# test1.net
KiCad netlist of a schematic drawn in EAGLE
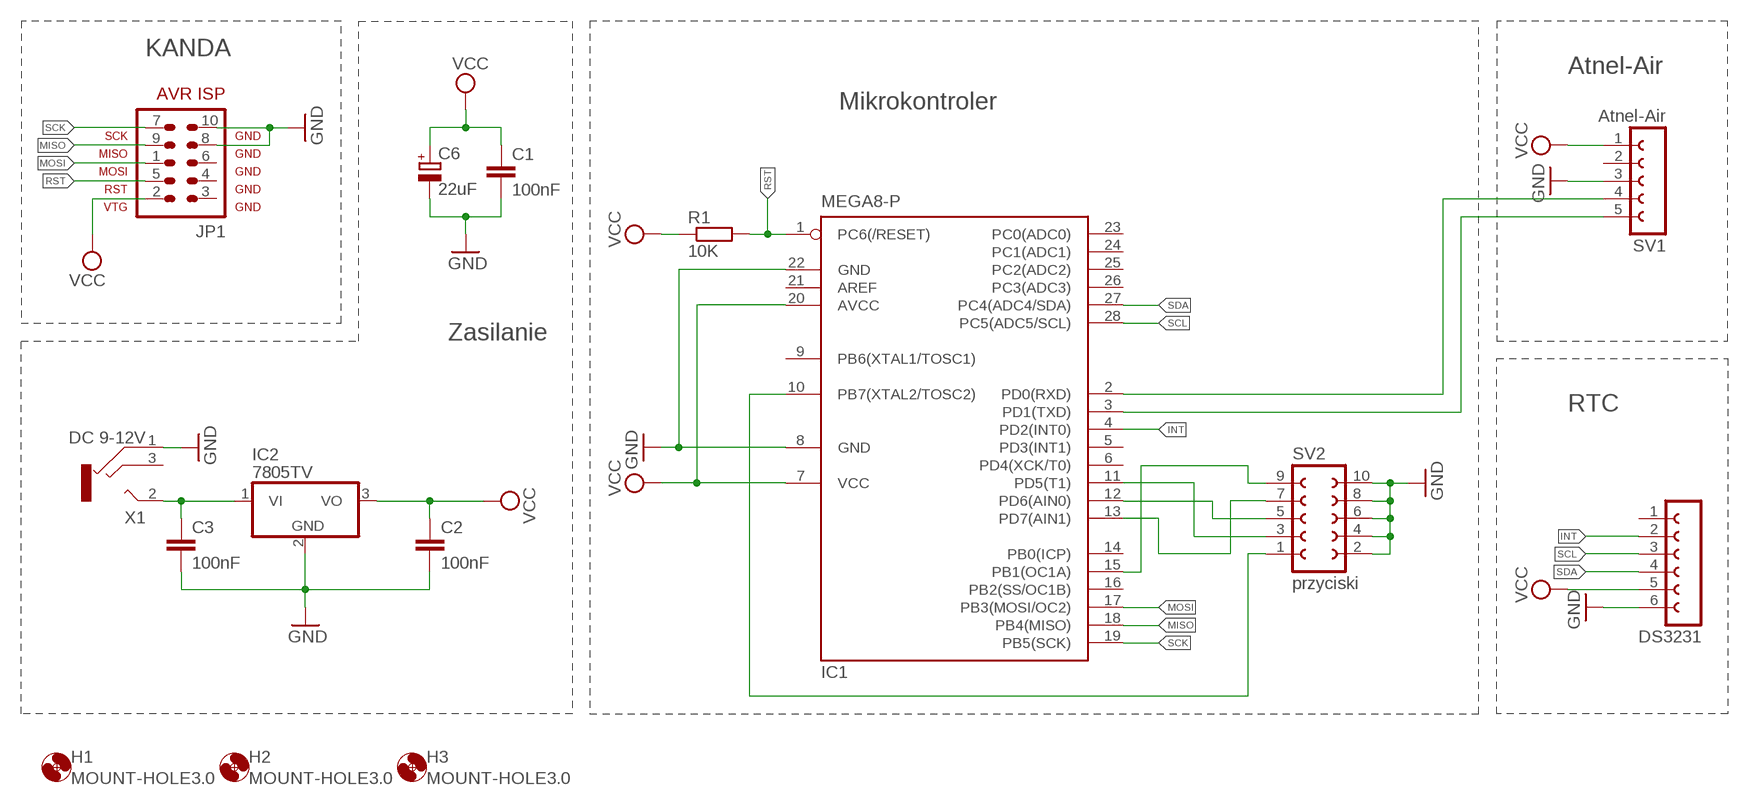
[diagram p0: schematic, sheet 1]

(export (version "E")
  (design (tool "Eeschema 10.0.6"))
  (components
    (comp (ref "C1")
      (value "100nF")
      (footprint "eagle-import:C025-024X044")
      (libsource (lib "eagle-import") (part "C-EU025-024X044"))
    )
    (comp (ref "C2")
      (value "100nF")
      (footprint "eagle-import:C025-024X044")
      (libsource (lib "eagle-import") (part "C-EU025-024X044"))
    )
    (comp (ref "C3")
      (value "100nF")
      (footprint "eagle-import:C025-024X044")
      (libsource (lib "eagle-import") (part "C-EU025-024X044"))
    )
    (comp (ref "C6")
      (value "22uF")
      (footprint "eagle-import:B45181A")
      (libsource (lib "eagle-import") (part "CPOL-EUB45181A"))
    )
    (comp (ref "DS3231")
      (value "FE06-1")
      (footprint "eagle-import:FE06")
      (libsource (lib "eagle-import") (part "FE06-1"))
    )
    (comp (ref "H1")
      (value "MOUNT-HOLE3.0")
      (footprint "eagle-import:3,0")
      (libsource (lib "eagle-import") (part "MOUNT-HOLE3.0"))
    )
    (comp (ref "H2")
      (value "MOUNT-HOLE3.0")
      (footprint "eagle-import:3,0")
      (libsource (lib "eagle-import") (part "MOUNT-HOLE3.0"))
    )
    (comp (ref "H3")
      (value "MOUNT-HOLE3.0")
      (footprint "eagle-import:3,0")
      (libsource (lib "eagle-import") (part "MOUNT-HOLE3.0"))
    )
    (comp (ref "IC1")
      (value "MEGA8-P")
      (footprint "eagle-import:DIL28-3")
      (libsource (lib "eagle-import") (part "MEGA8-P"))
    )
    (comp (ref "IC2")
      (value "7805TV")
      (footprint "eagle-import:TO220V")
      (libsource (lib "eagle-import") (part "78TV05"))
    )
    (comp (ref "JP1")
      (value "AVR-ISP-10")
      (footprint "eagle-import:AVR-ISP-10")
      (libsource (lib "eagle-import") (part "AVR-ISP-10"))
    )
    (comp (ref "R1")
      (value "10K")
      (footprint "eagle-import:0204V")
      (libsource (lib "eagle-import") (part "R-EU_0204/2V"))
    )
    (comp (ref "SV1")
      (value "Atnel-Air")
      (footprint "eagle-import:FE05-1")
      (libsource (lib "eagle-import") (part "FE05-1"))
    )
    (comp (ref "SV2")
      (value "przyciski")
      (footprint "eagle-import:FE05-2")
      (libsource (lib "eagle-import") (part "FE05-2"))
    )
    (comp (ref "X1")
      (value "DC 9-12V")
      (footprint "eagle-import:1501_05")
      (libsource (lib "eagle-import") (part "1501_04"))
    )
  )
  (nets
    (net (code "1") (name "GND") (class "Default")
      (node (ref "C1") (pin "2") (pinfunction "2_2") (pintype "passive"))
      (node (ref "C2") (pin "2") (pinfunction "2_2") (pintype "passive"))
      (node (ref "C3") (pin "2") (pinfunction "2_2") (pintype "passive"))
      (node (ref "C6") (pin "-") (pinfunction "-_-") (pintype "passive"))
      (node (ref "DS3231") (pin "6") (pinfunction "6_6") (pintype "passive"))
      (node (ref "IC1") (pin "22") (pinfunction "GND_22") (pintype "power_in"))
      (node (ref "IC1") (pin "8") (pinfunction "GND_8") (pintype "power_in"))
      (node (ref "IC2") (pin "2") (pinfunction "GND_2") (pintype "passive"))
      (node (ref "JP1") (pin "10") (pinfunction "10_10") (pintype "passive"))
      (node (ref "JP1") (pin "8") (pinfunction "8_8") (pintype "passive"))
      (node (ref "SV1") (pin "3") (pinfunction "3_3") (pintype "passive"))
      (node (ref "SV2") (pin "10") (pinfunction "10_10") (pintype "passive"))
      (node (ref "SV2") (pin "2") (pinfunction "2_2") (pintype "passive"))
      (node (ref "SV2") (pin "4") (pinfunction "4_4") (pintype "passive"))
      (node (ref "SV2") (pin "6") (pinfunction "6_6") (pintype "passive"))
      (node (ref "SV2") (pin "8") (pinfunction "8_8") (pintype "passive"))
      (node (ref "X1") (pin "1") (pinfunction "1_1") (pintype "passive"))
    )
    (net (code "2") (name "INT") (class "Default")
      (node (ref "DS3231") (pin "2") (pinfunction "2_2") (pintype "passive"))
      (node (ref "IC1") (pin "4") (pinfunction "PD2(INT0)_4") (pintype "bidirectional"))
    )
    (net (code "3") (name "MISO") (class "Default")
      (node (ref "IC1") (pin "18") (pinfunction "PB4(MISO)_18") (pintype "bidirectional"))
      (node (ref "JP1") (pin "9") (pinfunction "9_9") (pintype "passive"))
    )
    (net (code "4") (name "MOSI") (class "Default")
      (node (ref "IC1") (pin "17") (pinfunction "PB3(MOSI/OC2)_17") (pintype "bidirectional"))
      (node (ref "JP1") (pin "1") (pinfunction "1_1") (pintype "passive"))
    )
    (net (code "5") (name "Net-(IC1-PB1(OC1A))") (class "Default")
      (node (ref "IC1") (pin "15") (pinfunction "PB1(OC1A)_15") (pintype "bidirectional"))
      (node (ref "SV2") (pin "9") (pinfunction "9_9") (pintype "passive"))
    )
    (net (code "6") (name "Net-(IC1-PB7(XTAL2{slash}TOSC2))") (class "Default")
      (node (ref "IC1") (pin "10") (pinfunction "PB7(XTAL2/TOSC2)_10") (pintype "bidirectional"))
      (node (ref "SV2") (pin "1") (pinfunction "1_1") (pintype "passive"))
    )
    (net (code "7") (name "Net-(IC1-PD0(RXD))") (class "Default")
      (node (ref "IC1") (pin "2") (pinfunction "PD0(RXD)_2") (pintype "bidirectional"))
      (node (ref "SV1") (pin "4") (pinfunction "4_4") (pintype "passive"))
    )
    (net (code "8") (name "Net-(IC1-PD1(TXD))") (class "Default")
      (node (ref "IC1") (pin "3") (pinfunction "PD1(TXD)_3") (pintype "bidirectional"))
      (node (ref "SV1") (pin "5") (pinfunction "5_5") (pintype "passive"))
    )
    (net (code "9") (name "Net-(IC1-PD5(T1))") (class "Default")
      (node (ref "IC1") (pin "11") (pinfunction "PD5(T1)_11") (pintype "bidirectional"))
      (node (ref "SV2") (pin "3") (pinfunction "3_3") (pintype "passive"))
    )
    (net (code "10") (name "Net-(IC1-PD6(AIN0))") (class "Default")
      (node (ref "IC1") (pin "12") (pinfunction "PD6(AIN0)_12") (pintype "bidirectional"))
      (node (ref "SV2") (pin "5") (pinfunction "5_5") (pintype "passive"))
    )
    (net (code "11") (name "Net-(IC1-PD7(AIN1))") (class "Default")
      (node (ref "IC1") (pin "13") (pinfunction "PD7(AIN1)_13") (pintype "bidirectional"))
      (node (ref "SV2") (pin "7") (pinfunction "7_7") (pintype "passive"))
    )
    (net (code "12") (name "Net-(IC2-VI)") (class "Default")
      (node (ref "C3") (pin "1") (pinfunction "1_1") (pintype "passive"))
      (node (ref "IC2") (pin "1") (pinfunction "VI_1") (pintype "input"))
      (node (ref "X1") (pin "2") (pinfunction "2_2") (pintype "passive"))
    )
    (net (code "13") (name "RST") (class "Default")
      (node (ref "IC1") (pin "1") (pinfunction "PC6(/RESET)_1") (pintype "bidirectional"))
      (node (ref "JP1") (pin "5") (pinfunction "5_5") (pintype "passive"))
      (node (ref "R1") (pin "2") (pinfunction "2_2") (pintype "passive"))
    )
    (net (code "14") (name "SCK") (class "Default")
      (node (ref "IC1") (pin "19") (pinfunction "PB5(SCK)_19") (pintype "bidirectional"))
      (node (ref "JP1") (pin "7") (pinfunction "7_7") (pintype "passive"))
    )
    (net (code "15") (name "SCL") (class "Default")
      (node (ref "DS3231") (pin "3") (pinfunction "3_3") (pintype "passive"))
      (node (ref "IC1") (pin "28") (pinfunction "PC5(ADC5/SCL)_28") (pintype "bidirectional"))
    )
    (net (code "16") (name "SDA") (class "Default")
      (node (ref "DS3231") (pin "4") (pinfunction "4_4") (pintype "passive"))
      (node (ref "IC1") (pin "27") (pinfunction "PC4(ADC4/SDA)_27") (pintype "bidirectional"))
    )
    (net (code "17") (name "VCC") (class "Default")
      (node (ref "C1") (pin "1") (pinfunction "1_1") (pintype "passive"))
      (node (ref "C2") (pin "1") (pinfunction "1_1") (pintype "passive"))
      (node (ref "C6") (pin "+") (pinfunction "+_+") (pintype "passive"))
      (node (ref "DS3231") (pin "5") (pinfunction "5_5") (pintype "passive"))
      (node (ref "IC1") (pin "20") (pinfunction "AVCC_20") (pintype "power_in"))
      (node (ref "IC1") (pin "7") (pinfunction "VCC_7") (pintype "power_in"))
      (node (ref "IC2") (pin "3") (pinfunction "VO_3") (pintype "passive"))
      (node (ref "JP1") (pin "2") (pinfunction "2_2") (pintype "passive"))
      (node (ref "R1") (pin "1") (pinfunction "1_1") (pintype "passive"))
      (node (ref "SV1") (pin "1") (pinfunction "1_1") (pintype "passive"))
    )
    (net (code "18") (name "unconnected-(DS3231-Pad1)") (class "Default")
      (node (ref "DS3231") (pin "1") (pinfunction "1_1") (pintype "passive"))
    )
    (net (code "19") (name "unconnected-(IC1-AREF-Pad21)") (class "Default")
      (node (ref "IC1") (pin "21") (pinfunction "AREF_21") (pintype "passive"))
    )
    (net (code "20") (name "unconnected-(IC1-PB0(ICP)-Pad14)") (class "Default")
      (node (ref "IC1") (pin "14") (pinfunction "PB0(ICP)_14") (pintype "bidirectional"))
    )
    (net (code "21") (name "unconnected-(IC1-PB2(SS{slash}OC1B)-Pad16)") (class "Default")
      (node (ref "IC1") (pin "16") (pinfunction "PB2(SS/OC1B)_16") (pintype "bidirectional"))
    )
    (net (code "22") (name "unconnected-(IC1-PB6(XTAL1{slash}TOSC1)-Pad9)") (class "Default")
      (node (ref "IC1") (pin "9") (pinfunction "PB6(XTAL1/TOSC1)_9") (pintype "bidirectional"))
    )
    (net (code "23") (name "unconnected-(IC1-PC0(ADC0)-Pad23)") (class "Default")
      (node (ref "IC1") (pin "23") (pinfunction "PC0(ADC0)_23") (pintype "bidirectional"))
    )
    (net (code "24") (name "unconnected-(IC1-PC1(ADC1)-Pad24)") (class "Default")
      (node (ref "IC1") (pin "24") (pinfunction "PC1(ADC1)_24") (pintype "bidirectional"))
    )
    (net (code "25") (name "unconnected-(IC1-PC2(ADC2)-Pad25)") (class "Default")
      (node (ref "IC1") (pin "25") (pinfunction "PC2(ADC2)_25") (pintype "bidirectional"))
    )
    (net (code "26") (name "unconnected-(IC1-PC3(ADC3)-Pad26)") (class "Default")
      (node (ref "IC1") (pin "26") (pinfunction "PC3(ADC3)_26") (pintype "bidirectional"))
    )
    (net (code "27") (name "unconnected-(IC1-PD3(INT1)-Pad5)") (class "Default")
      (node (ref "IC1") (pin "5") (pinfunction "PD3(INT1)_5") (pintype "bidirectional"))
    )
    (net (code "28") (name "unconnected-(IC1-PD4(XCK{slash}T0)-Pad6)") (class "Default")
      (node (ref "IC1") (pin "6") (pinfunction "PD4(XCK/T0)_6") (pintype "bidirectional"))
    )
    (net (code "29") (name "unconnected-(JP1-Pad3)") (class "Default")
      (node (ref "JP1") (pin "3") (pinfunction "3_3") (pintype "passive"))
    )
    (net (code "30") (name "unconnected-(JP1-Pad4)") (class "Default")
      (node (ref "JP1") (pin "4") (pinfunction "4_4") (pintype "passive"))
    )
    (net (code "31") (name "unconnected-(JP1-Pad6)") (class "Default")
      (node (ref "JP1") (pin "6") (pinfunction "6_6") (pintype "passive"))
    )
    (net (code "32") (name "unconnected-(SV1-Pad2)") (class "Default")
      (node (ref "SV1") (pin "2") (pinfunction "2_2") (pintype "passive"))
    )
    (net (code "33") (name "unconnected-(X1-Pad3)") (class "Default")
      (node (ref "X1") (pin "3") (pinfunction "3_3") (pintype "passive"))
    )
  )
)
